# switch_mode.net
KiCad netlist of a schematic drawn in Altium Designer
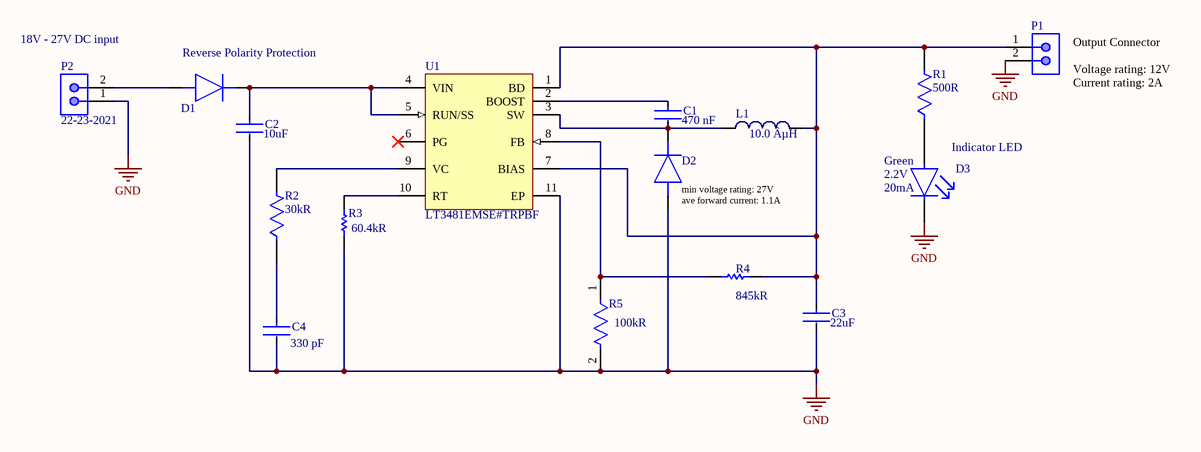
[diagram p0: switch_mode.SchDoc]

(export (version "E")
  (design (tool "Eeschema 10.0.6"))
  (components
    (comp (ref "C1")
      (value "470 nF")
      (footprint "FP-CC0805-0_85-MFG")
      (description "CAP CER 0.47UF 16V X7R 0805")
      (fields
        (field (name "MANUFACTURER") "Yageo")
        (field (name "OCTOPART") "https://octopart.com/cc0805kkx7r7bb474-yageo-42522863")
      )
      (libsource (lib "Altium Content Vault") (part "11868f565c42a9108669ba33697ecf6"))
    )
    (comp (ref "C2")
      (value "GRM31CR61H106KA12L")
      (footprint "FP-GRM31-0_2-MFG")
      (description "CAP CER 10UF 50V X5R 1206")
      (fields
        (field (name "OCTOPART") "https://octopart.com/grm31cr61h106ka12l-murata-18903335")
        (field (name "TOLERANCE") "10%")
        (field (name "CAPACITANCE") "10uF")
      )
      (libsource (lib "Altium Content Vault") (part "11868f565c42a9108669ba33697ecf6"))
    )
    (comp (ref "C3")
      (value "GRM31CR71A226KE15L")
      (footprint "FP-GRM31C-0_2-e0_3_0_8-MFG")
      (description "Chip Multilayer Ceramic Capacitors for General Purpose, 1206, 22uF, X7R, 15%, 10%, 10V")
      (fields
        (field (name "CAPACITANCE") "22uF")
        (field (name "VOLTAGE") "10V")
        (field (name "TOLERANCE") "10%")
      )
      (libsource (lib "Altium Content Vault") (part "02cd4be3c70576c341d710602a673aa"))
    )
    (comp (ref "C4")
      (value "CC1206KRX7R9BB331")
      (footprint "FP-CC1206-1_25-MFG")
      (description "CAP CER 330PF 50V X7R 1206")
      (fields
        (field (name "CAPACITANCE") "330 pF")
        (field (name "MANUFACTURER") "Yageo")
        (field (name "OCTOPART") "https://octopart.com/cc1206krx7r9bb331-yageo-193019")
      )
      (libsource (lib "Altium Content Vault") (part "11868f565c42a9108669ba33697ecf6"))
    )
    (comp (ref "D1")
      (value "B230-13-F")
      (footprint "footprints:DIONM5336X250N")
      (description "Diode")
      (fields (field (name "MOUSER PART NUMBER") "621-B230-F"))
      (libsource (lib "schematics") (part "B230-13-F"))
    )
    (comp (ref "D2")
      (value "B230-13-F")
      (footprint "footprints:DIONM5336X250N")
      (description "Diode")
      (fields (field (name "MOUSER PART NUMBER") "621-B230-F"))
      (libsource (lib "schematics") (part "B230-13-F"))
    )
    (comp (ref "D3")
      (value "597-3301-507F")
      (footprint "FP-597-3301-507F-MFG")
      (description "LED GREEN CLEAR 1208 SMD")
      (fields
        (field (name "OCTOPART") "https://octopart.com/597-3301-507f-dialight-117926")
        (field (name "MANUFACTURER") "Dialight")
        (field (name "FORWARD CURRENT") "20mA")
        (field (name "FORWARD VOLTAGE") "2.2V")
        (field (name "COLOUR") "Green")
      )
      (libsource (lib "Altium Content Vault") (part "8706943c75ba83719d021d2fdc84c58"))
    )
    (comp (ref "L1")
      (value "74404064100")
      (footprint "WE-LQS 6045")
      (description "WE-LQS SMD Power Inductor, L=10.0 µH")
      (fields (field (name "MANUFACTURER") "Wuerth Elektronik") (field (name "INDUCTANCE") "10.0 ÂµH"))
      (libsource (lib "Altium Content Vault") (part "WE-IND-INDUCTOR-2"))
    )
    (comp (ref "P1")
      (value "22-23-2021")
      (footprint "MOLX-22-23-2021_V")
      (libsource (lib "Altium Content Vault") (part "CN-1P-M-R2"))
    )
    (comp (ref "P2")
      (value "22-23-2021")
      (footprint "MOLX-22-23-2021_V")
      (libsource (lib "") (part "CN-1P-M-R2_1"))
    )
    (comp (ref "R1")
      (value "MCA12060D5000BP500")
      (footprint "FP-MCA1206-IPC_C")
      (description "Res MC Precision Thin Film 1206 500Ω 0.1% 0.25W ±25ppm/°C Molded Paper T/R")
      (fields (field (name "RESISTANCE") "500R") (field (name "TOLERANCE") "0.1%"))
      (libsource (lib "") (part "1029c3af85768c4190bb7ad29bc67b5_1"))
    )
    (comp (ref "R2")
      (value "CRCW080530K0FKEA")
      (footprint "FP-CRCW0805-e3-MFG")
      (description "RES Thick Film, 30kΩ, 1%, 0.125W, 100ppm/°C, 0805")
      (fields (field (name "TOLERANCE") "1%") (field (name "RESISTANCE") "30kR"))
      (libsource (lib "") (part "1029c3af85768c4190bb7ad29bc67b5_1"))
    )
    (comp (ref "R3")
      (value "CRCW080560K4FKEA")
      (footprint "RESC2013X50X30ML20T20")
      (fields (field (name "MANUFACTURER") "Vishay Dale") (field (name "RESISTANCE") "60.4kR"))
      (libsource (lib "Altium Content Vault") (part "RES"))
    )
    (comp (ref "R4")
      (value "CRCW0805845KFKEA")
      (footprint "RESC2013X50X30LL20T20")
      (fields (field (name "MANUFACTURER") "Vishay Dale") (field (name "RESISTANCE") "845kR"))
      (libsource (lib "Altium Content Vault") (part "RES"))
    )
    (comp (ref "R5")
      (value "CRCW0805100KFKEA")
      (footprint "FP-CRCW0805-e3-MFG")
      (description "RES Thick Film, 100kΩ, 1%, 0.125W, 100ppm/°C, 0805")
      (fields (field (name "RESISTANCE") "100kR") (field (name "TOLERANCE") "1%"))
      (libsource (lib "Altium Content Vault") (part "1029c3af85768c4190bb7ad29bc67b5"))
    )
    (comp (ref "U1")
      (value "LT3481EMSE#TRPBF")
      (footprint "LT-MSE-10-EDP-2060x1830TP_M")
      (fields (field (name "MANUFACTURER") "Linear Technology"))
      (libsource (lib "Altium Content Vault") (part "LT-LT3481-X-10"))
    )
  )
  (nets
    (net (code "1") (name "GND") (class "Default")
      (node (ref "C2") (pin "2") (pinfunction "2_2") (pintype "passive"))
      (node (ref "C3") (pin "2") (pinfunction "2_2") (pintype "passive"))
      (node (ref "C4") (pin "2") (pinfunction "2_2") (pintype "passive"))
      (node (ref "D2") (pin "1") (pinfunction "A_1") (pintype "passive"))
      (node (ref "D3") (pin "1") (pinfunction "C_1") (pintype "passive"))
      (node (ref "P1") (pin "2") (pinfunction "2_2") (pintype "passive"))
      (node (ref "P2") (pin "1") (pinfunction "1_1") (pintype "passive"))
      (node (ref "R3") (pin "1") (pinfunction "1_1") (pintype "passive"))
      (node (ref "R5") (pin "2") (pinfunction "2_2") (pintype "passive"))
      (node (ref "U1") (pin "11") (pinfunction "EP_11") (pintype "power_in"))
    )
    (net (code "2") (name "Net-(C4-Pad1)") (class "Default")
      (node (ref "C4") (pin "1") (pinfunction "1_1") (pintype "passive"))
      (node (ref "R2") (pin "1") (pinfunction "1_1") (pintype "passive"))
    )
    (net (code "3") (name "Net-(D1-A)") (class "Default")
      (node (ref "D1") (pin "1") (pinfunction "A_1") (pintype "passive"))
      (node (ref "P2") (pin "2") (pinfunction "2_2") (pintype "passive"))
    )
    (net (code "4") (name "Net-(D1-K)") (class "Default")
      (node (ref "C2") (pin "1") (pinfunction "1_1") (pintype "passive"))
      (node (ref "D1") (pin "2") (pinfunction "K_2") (pintype "passive"))
      (node (ref "U1") (pin "4") (pinfunction "VIN_4") (pintype "power_in"))
      (node (ref "U1") (pin "5") (pinfunction "RUN/SS_5") (pintype "input"))
    )
    (net (code "5") (name "Net-(D2-K)") (class "Default")
      (node (ref "C1") (pin "2") (pinfunction "2_2") (pintype "passive"))
      (node (ref "D2") (pin "2") (pinfunction "K_2") (pintype "passive"))
      (node (ref "L1") (pin "1") (pinfunction "1_1") (pintype "passive"))
      (node (ref "U1") (pin "3") (pinfunction "SW_3") (pintype "power_in"))
    )
    (net (code "6") (name "Net-(D3-A)") (class "Default")
      (node (ref "D3") (pin "2") (pinfunction "A_2") (pintype "passive"))
      (node (ref "R1") (pin "1") (pinfunction "1_1") (pintype "passive"))
    )
    (net (code "7") (name "Net-(U1-BD)") (class "Default")
      (node (ref "C3") (pin "1") (pinfunction "1_1") (pintype "passive"))
      (node (ref "L1") (pin "2") (pinfunction "2_2") (pintype "passive"))
      (node (ref "P1") (pin "1") (pinfunction "1_1") (pintype "passive"))
      (node (ref "R1") (pin "2") (pinfunction "2_2") (pintype "passive"))
      (node (ref "R4") (pin "1") (pinfunction "1_1") (pintype "passive"))
      (node (ref "U1") (pin "1") (pinfunction "BD_1") (pintype "power_in"))
      (node (ref "U1") (pin "7") (pinfunction "BIAS_7") (pintype "power_in"))
    )
    (net (code "8") (name "Net-(U1-BOOST)") (class "Default")
      (node (ref "C1") (pin "1") (pinfunction "1_1") (pintype "passive"))
      (node (ref "U1") (pin "2") (pinfunction "BOOST_2") (pintype "passive"))
    )
    (net (code "9") (name "Net-(U1-FB)") (class "Default")
      (node (ref "R4") (pin "2") (pinfunction "2_2") (pintype "passive"))
      (node (ref "R5") (pin "1") (pinfunction "1_1") (pintype "passive"))
      (node (ref "U1") (pin "8") (pinfunction "FB_8") (pintype "input"))
    )
    (net (code "10") (name "Net-(U1-RT)") (class "Default")
      (node (ref "R3") (pin "2") (pinfunction "2_2") (pintype "passive"))
      (node (ref "U1") (pin "10") (pinfunction "RT_10") (pintype "passive"))
    )
    (net (code "11") (name "Net-(U1-VC)") (class "Default")
      (node (ref "R2") (pin "2") (pinfunction "2_2") (pintype "passive"))
      (node (ref "U1") (pin "9") (pinfunction "VC_9") (pintype "passive"))
    )
    (net (code "12") (name "unconnected-(U1-PG-Pad6)") (class "Default")
      (node (ref "U1") (pin "6") (pinfunction "PG_6") (pintype "open_collector+no_connect"))
    )
  )
)
